# PCB-1__SCH_PHOENIX.net
KiCad netlist of a schematic drawn in EasyEDA
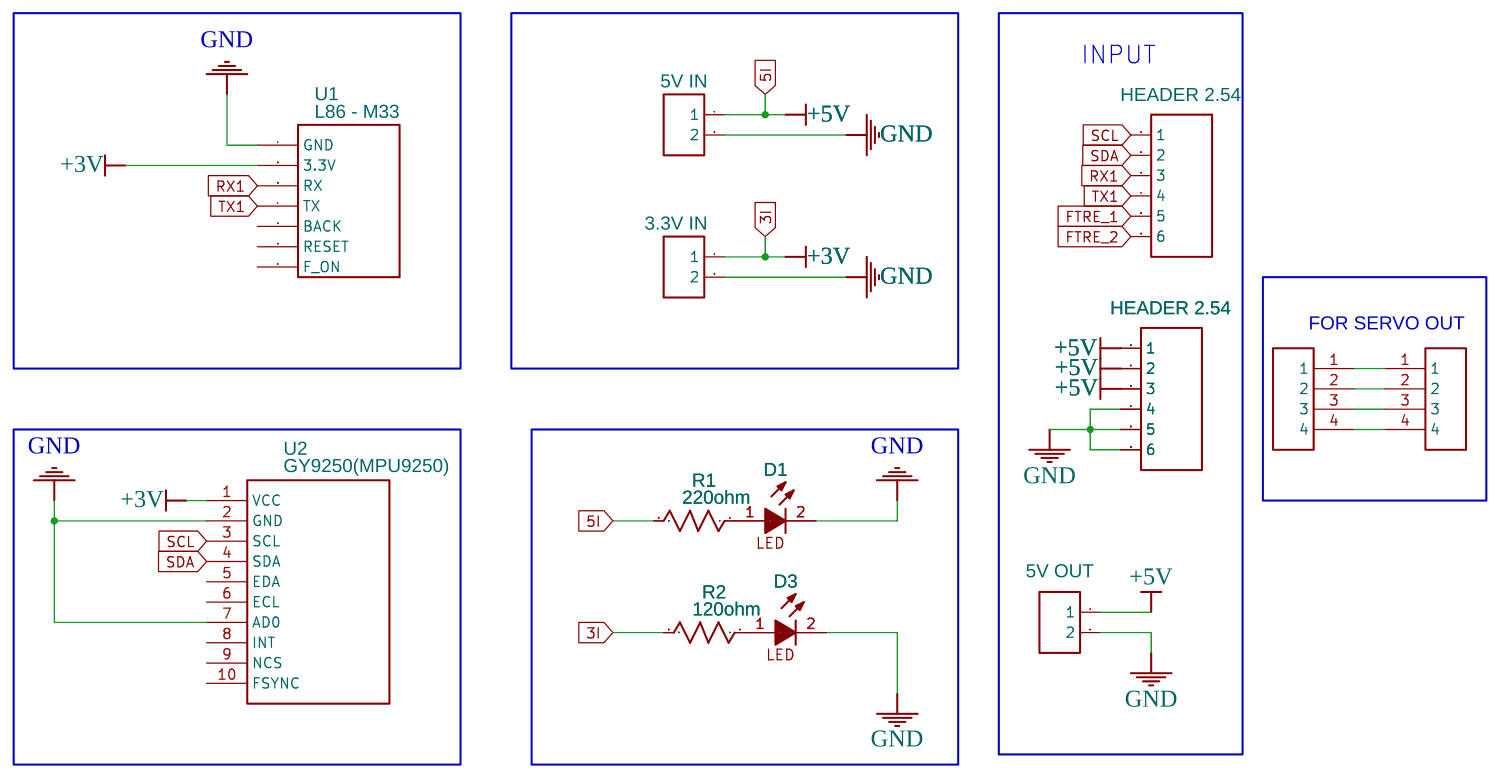
[diagram p0: schematic sheet]

(export (version "E")
  (design (tool "Eeschema 10.0.6"))
  (components
    (comp (ref "D1")
      (value "LED")
      (fields (field (name "Manufacturer Part") "5600") (field (name "Manufacturer") "VccLite"))
      (libsource (lib "") (part "LED"))
    )
    (comp (ref "D3")
      (value "LED")
      (fields (field (name "Manufacturer Part") "5600") (field (name "Manufacturer") "VccLite"))
      (libsource (lib "") (part "LED"))
    )
    (comp (ref "H1")
      (value "FOR SERVO OUT")
      (fields (field (name "Manufacturer Part") "2211S-04G") (field (name "Manufacturer") "MULTICOMP PRO"))
      (libsource (lib "") (part "B2B 2.54 MM HEADER_1"))
    )
    (comp (ref "H2")
      (value "FOR SERVO OUT")
      (fields (field (name "Manufacturer Part") "2211S-04G") (field (name "Manufacturer") "MULTICOMP PRO"))
      (libsource (lib "") (part "B2B 2.54 MM HEADER"))
    )
    (comp (ref "IN") (value "5V IN") (libsource (lib "") (part "CONN-TH_2P-P5.00")))
    (comp (ref "IN1") (value "5V OUT") (libsource (lib "") (part "CONN-TH_2P-P5.00")))
    (comp (ref "J1")
      (value "HEADER 2.54")
      (fields (field (name "Manufacturer Part") "2.54mm 1*20PHeader"))
      (libsource (lib "") (part "HEADER-MALE-2.54_1X6"))
    )
    (comp (ref "J2")
      (value "HEADER 2.54")
      (fields (field (name "Manufacturer Part") "2.54mm 1*20PHeader"))
      (libsource (lib "") (part "HEADER-MALE-2.54_1X6"))
    )
    (comp (ref "P1") (value "3.3V IN") (libsource (lib "") (part "CONN-TH_2P-P5.00_1")))
    (comp (ref "R1") (value "220ohm") (libsource (lib "") (part "R_0603_US")))
    (comp (ref "R2") (value "120ohm") (libsource (lib "") (part "R_0603_US")))
    (comp (ref "U1") (value "L86 - M33") (libsource (lib "") (part "BMP280 COPY")))
    (comp (ref "U2") (value "GY9250(MPU9250)") (libsource (lib "") (part "GY9250(MPU9250)")))
  )
  (nets
    (net (code "1") (name "3I") (class "Default")
      (node (ref "P1") (pin "1") (pinfunction "1_1") (pintype "unspecified"))
      (node (ref "R2") (pin "2") (pinfunction "2_2") (pintype "unspecified"))
      (node (ref "U1") (pin "6") (pinfunction "3.3V_6") (pintype "unspecified"))
      (node (ref "U2") (pin "1") (pinfunction "VCC_1") (pintype "unspecified"))
    )
    (net (code "2") (name "5I") (class "Default")
      (node (ref "IN") (pin "1") (pinfunction "1_1") (pintype "unspecified"))
      (node (ref "IN1") (pin "1") (pinfunction "1_1") (pintype "unspecified"))
      (node (ref "J2") (pin "1") (pinfunction "1_1") (pintype "input"))
      (node (ref "J2") (pin "2") (pinfunction "2_2") (pintype "input"))
      (node (ref "J2") (pin "3") (pinfunction "3_3") (pintype "input"))
      (node (ref "R1") (pin "2") (pinfunction "2_2") (pintype "unspecified"))
    )
    (net (code "3") (name "FTRE_1") (class "Default")
      (node (ref "J1") (pin "5") (pinfunction "5_5") (pintype "input"))
    )
    (net (code "4") (name "FTRE_2") (class "Default")
      (node (ref "J1") (pin "6") (pinfunction "6_6") (pintype "input"))
    )
    (net (code "5") (name "GND") (class "Default")
      (node (ref "D1") (pin "2") (pinfunction "K_2") (pintype "unspecified"))
      (node (ref "D3") (pin "2") (pinfunction "K_2") (pintype "unspecified"))
      (node (ref "IN") (pin "2") (pinfunction "2_2") (pintype "unspecified"))
      (node (ref "IN1") (pin "2") (pinfunction "2_2") (pintype "unspecified"))
      (node (ref "J2") (pin "4") (pinfunction "4_4") (pintype "input"))
      (node (ref "J2") (pin "5") (pinfunction "5_5") (pintype "input"))
      (node (ref "J2") (pin "6") (pinfunction "6_6") (pintype "input"))
      (node (ref "P1") (pin "2") (pinfunction "2_2") (pintype "unspecified"))
      (node (ref "U1") (pin "7") (pinfunction "GND_7") (pintype "unspecified"))
      (node (ref "U2") (pin "2") (pinfunction "GND_2") (pintype "unspecified"))
      (node (ref "U2") (pin "7") (pinfunction "AD0_7") (pintype "unspecified"))
    )
    (net (code "6") (name "Net-(D1-A)") (class "Default")
      (node (ref "D1") (pin "1") (pinfunction "A_1") (pintype "unspecified"))
      (node (ref "R1") (pin "1") (pinfunction "1_1") (pintype "unspecified"))
    )
    (net (code "7") (name "Net-(D3-A)") (class "Default")
      (node (ref "D3") (pin "1") (pinfunction "A_1") (pintype "unspecified"))
      (node (ref "R2") (pin "1") (pinfunction "1_1") (pintype "unspecified"))
    )
    (net (code "8") (name "Net-(H1-Pad1)") (class "Default")
      (node (ref "H1") (pin "1") (pinfunction "1_1") (pintype "unspecified"))
      (node (ref "H2") (pin "1") (pinfunction "1_1") (pintype "unspecified"))
    )
    (net (code "9") (name "Net-(H1-Pad2)") (class "Default")
      (node (ref "H1") (pin "2") (pinfunction "2_2") (pintype "unspecified"))
      (node (ref "H2") (pin "2") (pinfunction "2_2") (pintype "unspecified"))
    )
    (net (code "10") (name "Net-(H1-Pad3)") (class "Default")
      (node (ref "H1") (pin "3") (pinfunction "3_3") (pintype "unspecified"))
      (node (ref "H2") (pin "3") (pinfunction "3_3") (pintype "unspecified"))
    )
    (net (code "11") (name "Net-(H1-Pad4)") (class "Default")
      (node (ref "H1") (pin "4") (pinfunction "4_4") (pintype "unspecified"))
      (node (ref "H2") (pin "4") (pinfunction "4_4") (pintype "unspecified"))
    )
    (net (code "12") (name "RX1") (class "Default")
      (node (ref "J1") (pin "3") (pinfunction "3_3") (pintype "input"))
      (node (ref "U1") (pin "5") (pinfunction "RX_5") (pintype "unspecified"))
    )
    (net (code "13") (name "SCL") (class "Default")
      (node (ref "J1") (pin "1") (pinfunction "1_1") (pintype "input"))
      (node (ref "U2") (pin "3") (pinfunction "SCL_3") (pintype "unspecified"))
    )
    (net (code "14") (name "SDA") (class "Default")
      (node (ref "J1") (pin "2") (pinfunction "2_2") (pintype "input"))
      (node (ref "U2") (pin "4") (pinfunction "SDA_4") (pintype "unspecified"))
    )
    (net (code "15") (name "TX1") (class "Default")
      (node (ref "J1") (pin "4") (pinfunction "4_4") (pintype "input"))
      (node (ref "U1") (pin "4") (pinfunction "TX_4") (pintype "unspecified"))
    )
    (net (code "16") (name "unconnected-(U1-BACK-Pad3)") (class "Default")
      (node (ref "U1") (pin "3") (pinfunction "BACK_3") (pintype "unspecified"))
    )
    (net (code "17") (name "unconnected-(U1-F_ON-Pad1)") (class "Default")
      (node (ref "U1") (pin "1") (pinfunction "F_ON_1") (pintype "unspecified"))
    )
    (net (code "18") (name "unconnected-(U1-RESET-Pad2)") (class "Default")
      (node (ref "U1") (pin "2") (pinfunction "RESET_2") (pintype "unspecified"))
    )
    (net (code "19") (name "unconnected-(U2-ECL-Pad6)") (class "Default")
      (node (ref "U2") (pin "6") (pinfunction "ECL_6") (pintype "unspecified"))
    )
    (net (code "20") (name "unconnected-(U2-EDA-Pad5)") (class "Default")
      (node (ref "U2") (pin "5") (pinfunction "EDA_5") (pintype "unspecified"))
    )
    (net (code "21") (name "unconnected-(U2-FSYNC-Pad10)") (class "Default")
      (node (ref "U2") (pin "10") (pinfunction "FSYNC_10") (pintype "unspecified"))
    )
    (net (code "22") (name "unconnected-(U2-INT-Pad8)") (class "Default")
      (node (ref "U2") (pin "8") (pinfunction "INT_8") (pintype "unspecified"))
    )
    (net (code "23") (name "unconnected-(U2-NCS-Pad9)") (class "Default")
      (node (ref "U2") (pin "9") (pinfunction "NCS_9") (pintype "unspecified"))
    )
  )
)
